# SimpleNYT_prorto.net
KiCad netlist of a schematic drawn in Altium Designer
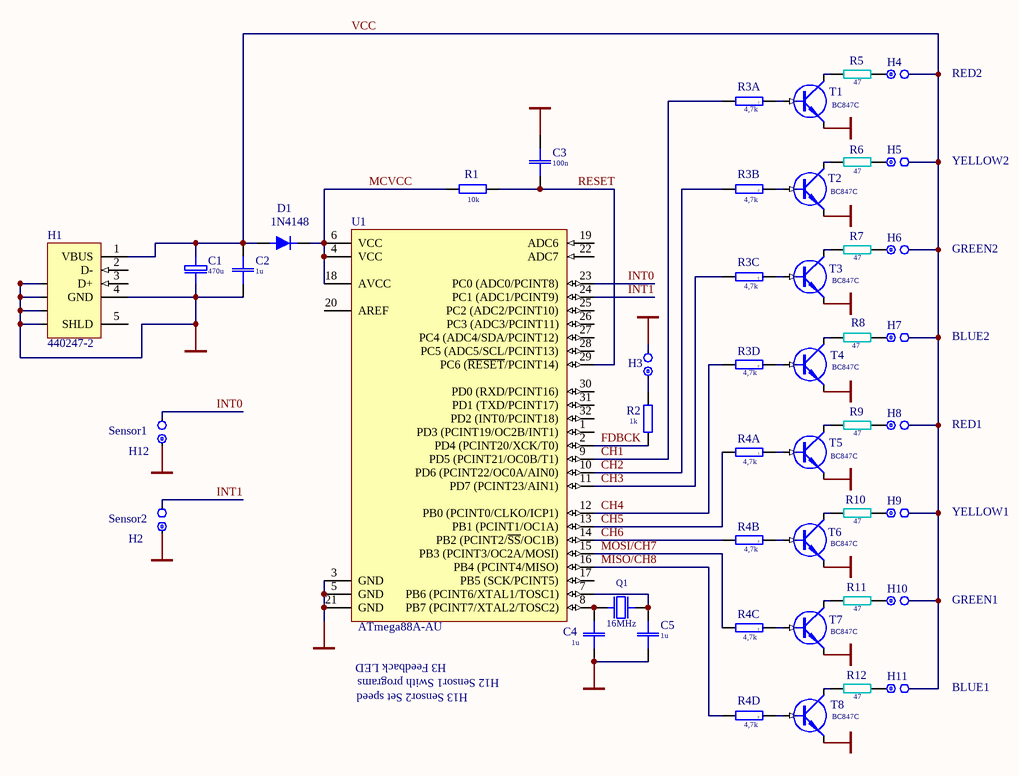
[diagram p0: SimpleNYT_prorto.SchDoc]

(export (version "E")
  (design (tool "Eeschema 10.0.6"))
  (components
    (comp (ref "C1")
      (value "470u")
      (footprint "El-d8-h12-F3.81")
      (description "16V")
      (libsource (lib "Cap-El") (part "470u-16V"))
    )
    (comp (ref "C2")
      (value "1u")
      (footprint "C1206(3216)")
      (description "SMD-1206")
      (libsource (lib "SMD-RCL") (part "C-1206"))
    )
    (comp (ref "C3")
      (value "100n")
      (footprint "C1206(3216)")
      (description "SMD-1206")
      (libsource (lib "SMD-RCL") (part "C-1206"))
    )
    (comp (ref "C4")
      (value "1u")
      (footprint "C1206(3216)")
      (description "SMD-1206")
      (libsource (lib "SMD-RCL") (part "C-1206"))
    )
    (comp (ref "C5")
      (value "1u")
      (footprint "C1206(3216)")
      (description "SMD-1206")
      (libsource (lib "SMD-RCL") (part "C-1206"))
    )
    (comp (ref "D1")
      (value "1N4148")
      (footprint "SOD323")
      (description "DO-35 75V 0.2A 1uS 4A 4nS")
      (libsource (lib "Diodes") (part "1N4148"))
    )
    (comp (ref "H1")
      (value "440247-2")
      (footprint "440247")
      (description "USB 2.0, Right Angle, SMT, B Type, Receptacle, 5 Position, Black")
      (fields (field (name "PUBLISHER") "Altium Limited"))
      (libsource (lib "AMP Serial Bus USB") (part "440247-2"))
    )
    (comp (ref "H2") (value "H-1x2") (footprint "J1x2") (libsource (lib "Connektor") (part "H-1x2")))
    (comp (ref "H3") (value "H-1x2") (footprint "J1x2") (libsource (lib "Connektor") (part "H-1x2")))
    (comp (ref "H4") (value "H-1x2") (footprint "J1x2") (libsource (lib "Connektor") (part "H-1x2")))
    (comp (ref "H5") (value "H-1x2") (footprint "J1x2") (libsource (lib "Connektor") (part "H-1x2")))
    (comp (ref "H6") (value "H-1x2") (footprint "J1x2") (libsource (lib "Connektor") (part "H-1x2")))
    (comp (ref "H7") (value "H-1x2") (footprint "J1x2") (libsource (lib "Connektor") (part "H-1x2")))
    (comp (ref "H8") (value "H-1x2") (footprint "J1x2") (libsource (lib "Connektor") (part "H-1x2")))
    (comp (ref "H9") (value "H-1x2") (footprint "J1x2") (libsource (lib "Connektor") (part "H-1x2")))
    (comp (ref "H10") (value "H-1x2") (footprint "J1x2") (libsource (lib "Connektor") (part "H-1x2")))
    (comp (ref "H11") (value "H-1x2") (footprint "J1x2") (libsource (lib "Connektor") (part "H-1x2")))
    (comp (ref "H12") (value "H-1x2") (footprint "J1x2") (libsource (lib "Connektor") (part "H-1x2")))
    (comp (ref "Q1") (value "16MHz") (footprint "HC49S") (libsource (lib "Devise") (part "Q")))
    (comp (ref "R1")
      (value "10k")
      (footprint "R0805")
      (description "SMD 0805 0.1W 5% 150V")
      (libsource (lib "SMD-RCL") (part "R-0805"))
    )
    (comp (ref "R2")
      (value "1k")
      (footprint "R0805")
      (description "SMD 0805 0.1W 5% 150V")
      (libsource (lib "SMD-RCL") (part "R-0805"))
    )
    (comp (ref "R3")
      (value "4,7k")
      (footprint "RM4x0603")
      (description "SMD 4RM-0603 1\\16W 5%")
      (libsource (lib "SMD-RCL") (part "4RM-0603"))
    )
    (comp (ref "R4")
      (value "4,7k")
      (footprint "RM4x0603")
      (description "SMD 4RM-0603 1\\16W 5%")
      (libsource (lib "SMD-RCL") (part "4RM-0603"))
    )
    (comp (ref "R5")
      (value "47")
      (footprint "R1206")
      (description "SMD 1206 0.125W 5% 200V")
      (libsource (lib "SMD-RCL") (part "R-1206"))
    )
    (comp (ref "R6")
      (value "47")
      (footprint "R1206")
      (description "SMD 1206 0.125W 5% 200V")
      (libsource (lib "SMD-RCL") (part "R-1206"))
    )
    (comp (ref "R7")
      (value "47")
      (footprint "R1206")
      (description "SMD 1206 0.125W 5% 200V")
      (libsource (lib "SMD-RCL") (part "R-1206"))
    )
    (comp (ref "R8")
      (value "47")
      (footprint "R1206")
      (description "SMD 1206 0.125W 5% 200V")
      (libsource (lib "SMD-RCL") (part "R-1206"))
    )
    (comp (ref "R9")
      (value "47")
      (footprint "R1206")
      (description "SMD 1206 0.125W 5% 200V")
      (libsource (lib "SMD-RCL") (part "R-1206"))
    )
    (comp (ref "R10")
      (value "47")
      (footprint "R1206")
      (description "SMD 1206 0.125W 5% 200V")
      (libsource (lib "SMD-RCL") (part "R-1206"))
    )
    (comp (ref "R11")
      (value "47")
      (footprint "R1206")
      (description "SMD 1206 0.125W 5% 200V")
      (libsource (lib "SMD-RCL") (part "R-1206"))
    )
    (comp (ref "R12")
      (value "47")
      (footprint "R1206")
      (description "SMD 1206 0.125W 5% 200V")
      (libsource (lib "SMD-RCL") (part "R-1206"))
    )
    (comp (ref "T1")
      (value "BC847C")
      (footprint "SOT23")
      (description "SMD-SOT23")
      (libsource (lib "BJT") (part "BC847C"))
    )
    (comp (ref "T2")
      (value "BC847C")
      (footprint "SOT23")
      (description "SMD-SOT23")
      (libsource (lib "BJT") (part "BC847C"))
    )
    (comp (ref "T3")
      (value "BC847C")
      (footprint "SOT23")
      (description "SMD-SOT23")
      (libsource (lib "BJT") (part "BC847C"))
    )
    (comp (ref "T4")
      (value "BC847C")
      (footprint "SOT23")
      (description "SMD-SOT23")
      (libsource (lib "BJT") (part "BC847C"))
    )
    (comp (ref "T5")
      (value "BC847C")
      (footprint "SOT23")
      (description "SMD-SOT23")
      (libsource (lib "BJT") (part "BC847C"))
    )
    (comp (ref "T6")
      (value "BC847C")
      (footprint "SOT23")
      (description "SMD-SOT23")
      (libsource (lib "BJT") (part "BC847C"))
    )
    (comp (ref "T7")
      (value "BC847C")
      (footprint "SOT23")
      (description "SMD-SOT23")
      (libsource (lib "BJT") (part "BC847C"))
    )
    (comp (ref "T8")
      (value "BC847C")
      (footprint "SOT23")
      (description "SMD-SOT23")
      (libsource (lib "BJT") (part "BC847C"))
    )
    (comp (ref "U1")
      (value "ATmega88A-AU")
      (footprint "32A_N")
      (libsource (lib "Atmel Microcontroller megaAVR") (part "ATmega88A-AU"))
    )
  )
  (nets
    (net (code "1") (name "/CH1") (class "Default")
      (node (ref "R3") (pin "8") (pinfunction "8_8") (pintype "passive"))
      (node (ref "U1") (pin "9") (pinfunction "PD5_(PCINT21/OC0B/T1)_9") (pintype "bidirectional"))
    )
    (net (code "2") (name "/CH2") (class "Default")
      (node (ref "R3") (pin "7") (pinfunction "7_7") (pintype "passive"))
      (node (ref "U1") (pin "10") (pinfunction "PD6_(PCINT22/OC0A/AIN0)_10") (pintype "bidirectional"))
    )
    (net (code "3") (name "/CH3") (class "Default")
      (node (ref "R3") (pin "6") (pinfunction "6_6") (pintype "passive"))
      (node (ref "U1") (pin "11") (pinfunction "PD7_(PCINT23/AIN1)_11") (pintype "bidirectional"))
    )
    (net (code "4") (name "/CH4") (class "Default")
      (node (ref "R3") (pin "5") (pinfunction "5_5") (pintype "passive"))
      (node (ref "U1") (pin "12") (pinfunction "PB0_(PCINT0/CLKO/ICP1)_12") (pintype "bidirectional"))
    )
    (net (code "5") (name "/CH5") (class "Default")
      (node (ref "R4") (pin "8") (pinfunction "8_8") (pintype "passive"))
      (node (ref "U1") (pin "13") (pinfunction "PB1_(PCINT1/OC1A)_13") (pintype "bidirectional"))
    )
    (net (code "6") (name "/CH6") (class "Default")
      (node (ref "R4") (pin "7") (pinfunction "7_7") (pintype "passive"))
      (node (ref "U1") (pin "14") (pinfunction "PB2_(PCINT2/~{SS}/OC1B)_14") (pintype "bidirectional"))
    )
    (net (code "7") (name "/FDBCK") (class "Default")
      (node (ref "R2") (pin "2") (pinfunction "2_2") (pintype "passive"))
      (node (ref "U1") (pin "2") (pinfunction "PD4_(PCINT20/XCK/T0)_2") (pintype "bidirectional"))
    )
    (net (code "8") (name "/INT0") (class "Default")
      (node (ref "H12") (pin "2") (pinfunction "2_2") (pintype "passive"))
      (node (ref "U1") (pin "23") (pinfunction "PC0_(ADC0/PCINT8)_23") (pintype "bidirectional"))
    )
    (net (code "9") (name "/INT1") (class "Default")
      (node (ref "H2") (pin "2") (pinfunction "2_2") (pintype "passive"))
      (node (ref "U1") (pin "24") (pinfunction "PC1_(ADC1/PCINT9)_24") (pintype "bidirectional"))
    )
    (net (code "10") (name "/MCVCC") (class "Default")
      (node (ref "D1") (pin "2") (pinfunction "C_2") (pintype "passive"))
      (node (ref "R1") (pin "2") (pinfunction "2_2") (pintype "passive"))
      (node (ref "U1") (pin "18") (pinfunction "AVCC_18") (pintype "power_in"))
      (node (ref "U1") (pin "4") (pinfunction "VCC_4") (pintype "power_in"))
      (node (ref "U1") (pin "6") (pinfunction "VCC_6") (pintype "power_in"))
    )
    (net (code "11") (name "/MISO{slash}CH8") (class "Default")
      (node (ref "R4") (pin "5") (pinfunction "5_5") (pintype "passive"))
      (node (ref "U1") (pin "16") (pinfunction "PB4_(PCINT4/MISO)_16") (pintype "bidirectional"))
    )
    (net (code "12") (name "/MOSI{slash}CH7") (class "Default")
      (node (ref "R4") (pin "6") (pinfunction "6_6") (pintype "passive"))
      (node (ref "U1") (pin "15") (pinfunction "PB3_(PCINT3/OC2A/MOSI)_15") (pintype "bidirectional"))
    )
    (net (code "13") (name "/RESET") (class "Default")
      (node (ref "C3") (pin "2") (pinfunction "2_2") (pintype "passive"))
      (node (ref "R1") (pin "1") (pinfunction "1_1") (pintype "passive"))
      (node (ref "U1") (pin "29") (pinfunction "PC6_(~{RESET}/PCINT14)_29") (pintype "bidirectional"))
    )
    (net (code "14") (name "/VCC") (class "Default")
      (node (ref "C1") (pin "1") (pinfunction "1_1") (pintype "passive"))
      (node (ref "C2") (pin "1") (pinfunction "1_1") (pintype "passive"))
      (node (ref "D1") (pin "1") (pinfunction "A_1") (pintype "passive"))
      (node (ref "H1") (pin "1") (pinfunction "VBUS_1") (pintype "power_in"))
      (node (ref "H10") (pin "2") (pinfunction "2_2") (pintype "passive"))
      (node (ref "H11") (pin "2") (pinfunction "2_2") (pintype "passive"))
      (node (ref "H4") (pin "2") (pinfunction "2_2") (pintype "passive"))
      (node (ref "H5") (pin "2") (pinfunction "2_2") (pintype "passive"))
      (node (ref "H6") (pin "2") (pinfunction "2_2") (pintype "passive"))
      (node (ref "H7") (pin "2") (pinfunction "2_2") (pintype "passive"))
      (node (ref "H8") (pin "2") (pinfunction "2_2") (pintype "passive"))
      (node (ref "H9") (pin "2") (pinfunction "2_2") (pintype "passive"))
    )
    (net (code "15") (name "GND") (class "Default")
      (node (ref "C1") (pin "2") (pinfunction "2_2") (pintype "passive"))
      (node (ref "C2") (pin "2") (pinfunction "2_2") (pintype "passive"))
      (node (ref "C3") (pin "1") (pinfunction "1_1") (pintype "passive"))
      (node (ref "C4") (pin "2") (pinfunction "2_2") (pintype "passive"))
      (node (ref "C5") (pin "2") (pinfunction "2_2") (pintype "passive"))
      (node (ref "H1") (pin "4") (pinfunction "GND_4") (pintype "power_in"))
      (node (ref "H1") (pin "6") (pinfunction "SHLD_6") (pintype "passive"))
      (node (ref "H1") (pin "7") (pinfunction "SHLD_7") (pintype "passive"))
      (node (ref "H1") (pin "8") (pinfunction "SHLD_8") (pintype "passive"))
      (node (ref "H1") (pin "9") (pinfunction "SHLD_9") (pintype "passive"))
      (node (ref "H12") (pin "1") (pinfunction "1_1") (pintype "passive"))
      (node (ref "H2") (pin "1") (pinfunction "1_1") (pintype "passive"))
      (node (ref "H3") (pin "2") (pinfunction "2_2") (pintype "passive"))
      (node (ref "T1") (pin "2") (pinfunction "E_2") (pintype "open_emitter"))
      (node (ref "T2") (pin "2") (pinfunction "E_2") (pintype "open_emitter"))
      (node (ref "T3") (pin "2") (pinfunction "E_2") (pintype "open_emitter"))
      (node (ref "T4") (pin "2") (pinfunction "E_2") (pintype "open_emitter"))
      (node (ref "T5") (pin "2") (pinfunction "E_2") (pintype "open_emitter"))
      (node (ref "T6") (pin "2") (pinfunction "E_2") (pintype "open_emitter"))
      (node (ref "T7") (pin "2") (pinfunction "E_2") (pintype "open_emitter"))
      (node (ref "T8") (pin "2") (pinfunction "E_2") (pintype "open_emitter"))
      (node (ref "U1") (pin "21") (pinfunction "GND_21") (pintype "power_in"))
      (node (ref "U1") (pin "3") (pinfunction "GND_3") (pintype "power_in"))
      (node (ref "U1") (pin "5") (pinfunction "GND_5") (pintype "power_in"))
    )
    (net (code "16") (name "Net-(H3-Pad1)") (class "Default")
      (node (ref "H3") (pin "1") (pinfunction "1_1") (pintype "passive"))
      (node (ref "R2") (pin "1") (pinfunction "1_1") (pintype "passive"))
    )
    (net (code "17") (name "Net-(H4-Pad1)") (class "Default")
      (node (ref "H4") (pin "1") (pinfunction "1_1") (pintype "passive"))
      (node (ref "R5") (pin "1") (pinfunction "1_1") (pintype "passive"))
    )
    (net (code "18") (name "Net-(H5-Pad1)") (class "Default")
      (node (ref "H5") (pin "1") (pinfunction "1_1") (pintype "passive"))
      (node (ref "R6") (pin "1") (pinfunction "1_1") (pintype "passive"))
    )
    (net (code "19") (name "Net-(H6-Pad1)") (class "Default")
      (node (ref "H6") (pin "1") (pinfunction "1_1") (pintype "passive"))
      (node (ref "R7") (pin "1") (pinfunction "1_1") (pintype "passive"))
    )
    (net (code "20") (name "Net-(H7-Pad1)") (class "Default")
      (node (ref "H7") (pin "1") (pinfunction "1_1") (pintype "passive"))
      (node (ref "R8") (pin "1") (pinfunction "1_1") (pintype "passive"))
    )
    (net (code "21") (name "Net-(H8-Pad1)") (class "Default")
      (node (ref "H8") (pin "1") (pinfunction "1_1") (pintype "passive"))
      (node (ref "R9") (pin "1") (pinfunction "1_1") (pintype "passive"))
    )
    (net (code "22") (name "Net-(H9-Pad1)") (class "Default")
      (node (ref "H9") (pin "1") (pinfunction "1_1") (pintype "passive"))
      (node (ref "R10") (pin "1") (pinfunction "1_1") (pintype "passive"))
    )
    (net (code "23") (name "Net-(H10-Pad1)") (class "Default")
      (node (ref "H10") (pin "1") (pinfunction "1_1") (pintype "passive"))
      (node (ref "R11") (pin "1") (pinfunction "1_1") (pintype "passive"))
    )
    (net (code "24") (name "Net-(H11-Pad1)") (class "Default")
      (node (ref "H11") (pin "1") (pinfunction "1_1") (pintype "passive"))
      (node (ref "R12") (pin "1") (pinfunction "1_1") (pintype "passive"))
    )
    (net (code "25") (name "Net-(T1-B)") (class "Default")
      (node (ref "R3") (pin "1") (pinfunction "1_1") (pintype "passive"))
      (node (ref "T1") (pin "1") (pinfunction "B_1") (pintype "input"))
    )
    (net (code "26") (name "Net-(T1-C)") (class "Default")
      (node (ref "R5") (pin "2") (pinfunction "2_2") (pintype "passive"))
      (node (ref "T1") (pin "3") (pinfunction "C_3") (pintype "open_collector"))
    )
    (net (code "27") (name "Net-(T2-B)") (class "Default")
      (node (ref "R3") (pin "2") (pinfunction "2_2") (pintype "passive"))
      (node (ref "T2") (pin "1") (pinfunction "B_1") (pintype "input"))
    )
    (net (code "28") (name "Net-(T2-C)") (class "Default")
      (node (ref "R6") (pin "2") (pinfunction "2_2") (pintype "passive"))
      (node (ref "T2") (pin "3") (pinfunction "C_3") (pintype "open_collector"))
    )
    (net (code "29") (name "Net-(T3-B)") (class "Default")
      (node (ref "R3") (pin "3") (pinfunction "3_3") (pintype "passive"))
      (node (ref "T3") (pin "1") (pinfunction "B_1") (pintype "input"))
    )
    (net (code "30") (name "Net-(T3-C)") (class "Default")
      (node (ref "R7") (pin "2") (pinfunction "2_2") (pintype "passive"))
      (node (ref "T3") (pin "3") (pinfunction "C_3") (pintype "open_collector"))
    )
    (net (code "31") (name "Net-(T4-B)") (class "Default")
      (node (ref "R3") (pin "4") (pinfunction "4_4") (pintype "passive"))
      (node (ref "T4") (pin "1") (pinfunction "B_1") (pintype "input"))
    )
    (net (code "32") (name "Net-(T4-C)") (class "Default")
      (node (ref "R8") (pin "2") (pinfunction "2_2") (pintype "passive"))
      (node (ref "T4") (pin "3") (pinfunction "C_3") (pintype "open_collector"))
    )
    (net (code "33") (name "Net-(T5-B)") (class "Default")
      (node (ref "R4") (pin "1") (pinfunction "1_1") (pintype "passive"))
      (node (ref "T5") (pin "1") (pinfunction "B_1") (pintype "input"))
    )
    (net (code "34") (name "Net-(T5-C)") (class "Default")
      (node (ref "R9") (pin "2") (pinfunction "2_2") (pintype "passive"))
      (node (ref "T5") (pin "3") (pinfunction "C_3") (pintype "open_collector"))
    )
    (net (code "35") (name "Net-(T6-B)") (class "Default")
      (node (ref "R4") (pin "2") (pinfunction "2_2") (pintype "passive"))
      (node (ref "T6") (pin "1") (pinfunction "B_1") (pintype "input"))
    )
    (net (code "36") (name "Net-(T6-C)") (class "Default")
      (node (ref "R10") (pin "2") (pinfunction "2_2") (pintype "passive"))
      (node (ref "T6") (pin "3") (pinfunction "C_3") (pintype "open_collector"))
    )
    (net (code "37") (name "Net-(T7-B)") (class "Default")
      (node (ref "R4") (pin "3") (pinfunction "3_3") (pintype "passive"))
      (node (ref "T7") (pin "1") (pinfunction "B_1") (pintype "input"))
    )
    (net (code "38") (name "Net-(T7-C)") (class "Default")
      (node (ref "R11") (pin "2") (pinfunction "2_2") (pintype "passive"))
      (node (ref "T7") (pin "3") (pinfunction "C_3") (pintype "open_collector"))
    )
    (net (code "39") (name "Net-(T8-B)") (class "Default")
      (node (ref "R4") (pin "4") (pinfunction "4_4") (pintype "passive"))
      (node (ref "T8") (pin "1") (pinfunction "B_1") (pintype "input"))
    )
    (net (code "40") (name "Net-(T8-C)") (class "Default")
      (node (ref "R12") (pin "2") (pinfunction "2_2") (pintype "passive"))
      (node (ref "T8") (pin "3") (pinfunction "C_3") (pintype "open_collector"))
    )
    (net (code "41") (name "Net-(U1-PB6_(PCINT6{slash}XTAL1{slash}TOSC1))") (class "Default")
      (node (ref "C5") (pin "1") (pinfunction "1_1") (pintype "passive"))
      (node (ref "Q1") (pin "1") (pinfunction "1_1") (pintype "passive"))
      (node (ref "U1") (pin "7") (pinfunction "PB6_(PCINT6/XTAL1/TOSC1)_7") (pintype "bidirectional"))
    )
    (net (code "42") (name "Net-(U1-PB7_(PCINT7{slash}XTAL2{slash}TOSC2))") (class "Default")
      (node (ref "C4") (pin "1") (pinfunction "1_1") (pintype "passive"))
      (node (ref "Q1") (pin "2") (pinfunction "2_2") (pintype "passive"))
      (node (ref "U1") (pin "8") (pinfunction "PB7_(PCINT7/XTAL2/TOSC2)_8") (pintype "bidirectional"))
    )
    (net (code "43") (name "unconnected-(H1-D+-Pad3)") (class "Default")
      (node (ref "H1") (pin "3") (pinfunction "D+_3") (pintype "input"))
    )
    (net (code "44") (name "unconnected-(H1-D--Pad2)") (class "Default")
      (node (ref "H1") (pin "2") (pinfunction "D-_2") (pintype "input"))
    )
    (net (code "45") (name "unconnected-(H1-SHLD-Pad5)") (class "Default")
      (node (ref "H1") (pin "5") (pinfunction "SHLD_5") (pintype "passive"))
    )
    (net (code "46") (name "unconnected-(U1-ADC6-Pad19)") (class "Default")
      (node (ref "U1") (pin "19") (pinfunction "ADC6_19") (pintype "input"))
    )
    (net (code "47") (name "unconnected-(U1-ADC7-Pad22)") (class "Default")
      (node (ref "U1") (pin "22") (pinfunction "ADC7_22") (pintype "input"))
    )
    (net (code "48") (name "unconnected-(U1-AREF-Pad20)") (class "Default")
      (node (ref "U1") (pin "20") (pinfunction "AREF_20") (pintype "passive"))
    )
    (net (code "49") (name "unconnected-(U1-PB5_(SCK{slash}PCINT5)-Pad17)") (class "Default")
      (node (ref "U1") (pin "17") (pinfunction "PB5_(SCK/PCINT5)_17") (pintype "bidirectional"))
    )
    (net (code "50") (name "unconnected-(U1-PC2_(ADC2{slash}PCINT10)-Pad25)") (class "Default")
      (node (ref "U1") (pin "25") (pinfunction "PC2_(ADC2/PCINT10)_25") (pintype "bidirectional"))
    )
    (net (code "51") (name "unconnected-(U1-PC3_(ADC3{slash}PCINT11)-Pad26)") (class "Default")
      (node (ref "U1") (pin "26") (pinfunction "PC3_(ADC3/PCINT11)_26") (pintype "bidirectional"))
    )
    (net (code "52") (name "unconnected-(U1-PC4_(ADC4{slash}SDA{slash}PCINT12)-Pad27)") (class "Default")
      (node (ref "U1") (pin "27") (pinfunction "PC4_(ADC4/SDA/PCINT12)_27") (pintype "bidirectional"))
    )
    (net (code "53") (name "unconnected-(U1-PC5_(ADC5{slash}SCL{slash}PCINT13)-Pad28)") (class "Default")
      (node (ref "U1") (pin "28") (pinfunction "PC5_(ADC5/SCL/PCINT13)_28") (pintype "bidirectional"))
    )
    (net (code "54") (name "unconnected-(U1-PD0_(RXD{slash}PCINT16)-Pad30)") (class "Default")
      (node (ref "U1") (pin "30") (pinfunction "PD0_(RXD/PCINT16)_30") (pintype "bidirectional"))
    )
    (net (code "55") (name "unconnected-(U1-PD1_(TXD{slash}PCINT17)-Pad31)") (class "Default")
      (node (ref "U1") (pin "31") (pinfunction "PD1_(TXD/PCINT17)_31") (pintype "bidirectional"))
    )
    (net (code "56") (name "unconnected-(U1-PD2_(INT0{slash}PCINT18)-Pad32)") (class "Default")
      (node (ref "U1") (pin "32") (pinfunction "PD2_(INT0/PCINT18)_32") (pintype "bidirectional"))
    )
    (net (code "57") (name "unconnected-(U1-PD3_(PCINT19{slash}OC2B{slash}INT1)-Pad1)") (class "Default")
      (node (ref "U1") (pin "1") (pinfunction "PD3_(PCINT19/OC2B/INT1)_1") (pintype "bidirectional"))
    )
  )
)
